# PlugV2.net
KiCad netlist of a schematic drawn in EAGLE
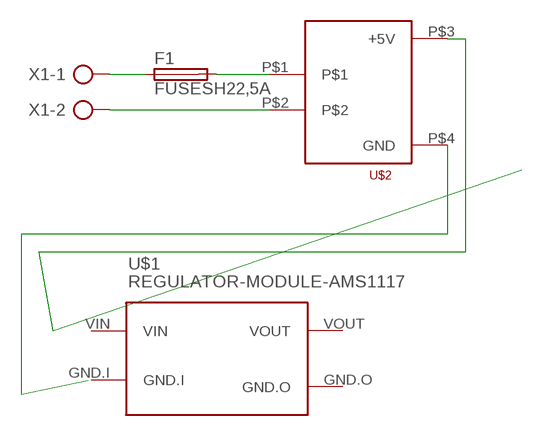
[diagram p0: schematic, sheet 1]

(export (version "E")
  (design (tool "Eeschema 10.0.6"))
  (components
    (comp (ref "F1")
      (value "FUSESH22,5A")
      (footprint "eagle-import:SH22,5A")
      (libsource (lib "eagle-import") (part "FUSESH22,5A"))
    )
    (comp (ref "U$1")
      (value "REGULATOR-MODULE-AMS1117")
      (footprint "eagle-import:REGULATOR-MODULE-AMS1117")
      (libsource (lib "eagle-import") (part "REGULATOR-MODULE-AMS1117"))
    )
    (comp (ref "U$2")
      (value "HLK-PM01")
      (footprint "eagle-import:HLK-PM01")
      (libsource (lib "eagle-import") (part "HLK-PM01"))
    )
    (comp (ref "X1")
      (value "AK300/2")
      (footprint "eagle-import:AK300_2")
      (libsource (lib "eagle-import") (part "AK300/2"))
    )
  )
  (nets
    (net (code "1") (name "Net-(F1-Pad2)") (class "Default")
      (node (ref "F1") (pin "2") (pinfunction "2_2") (pintype "passive"))
      (node (ref "U$2") (pin "P$1") (pinfunction "P$1_P$1") (pintype "bidirectional"))
    )
    (net (code "2") (name "Net-(X1A-KL)") (class "Default")
      (node (ref "F1") (pin "1") (pinfunction "1_1") (pintype "passive"))
      (node (ref "X1") (pin "1") (pinfunction "KL_1") (pintype "passive"))
    )
    (net (code "3") (name "Net-(X1B-KL)") (class "Default")
      (node (ref "U$2") (pin "P$2") (pinfunction "P$2_P$2") (pintype "bidirectional"))
      (node (ref "X1") (pin "2") (pinfunction "KL_2") (pintype "passive"))
    )
    (net (code "4") (name "unconnected-(U$1-PadGND.I)") (class "Default")
      (node (ref "U$1") (pin "GND.I") (pinfunction "GND.I_GND.I") (pintype "bidirectional"))
    )
    (net (code "5") (name "unconnected-(U$1-PadGND.O)") (class "Default")
      (node (ref "U$1") (pin "GND.O") (pinfunction "GND.O_GND.O") (pintype "bidirectional"))
    )
    (net (code "6") (name "unconnected-(U$1-PadVIN)") (class "Default")
      (node (ref "U$1") (pin "VIN") (pinfunction "VIN_VIN") (pintype "bidirectional"))
    )
    (net (code "7") (name "unconnected-(U$1-PadVOUT)") (class "Default")
      (node (ref "U$1") (pin "VOUT") (pinfunction "VOUT_VOUT") (pintype "bidirectional"))
    )
    (net (code "8") (name "unconnected-(U$2-+5V-PadP$3)") (class "Default")
      (node (ref "U$2") (pin "P$3") (pinfunction "+5V_P$3") (pintype "bidirectional"))
    )
    (net (code "9") (name "unconnected-(U$2-GND-PadP$4)") (class "Default")
      (node (ref "U$2") (pin "P$4") (pinfunction "GND_P$4") (pintype "bidirectional"))
    )
  )
)
